# SCH_New_Project_2023-10-16.net
KiCad netlist of a schematic drawn in EasyEDA
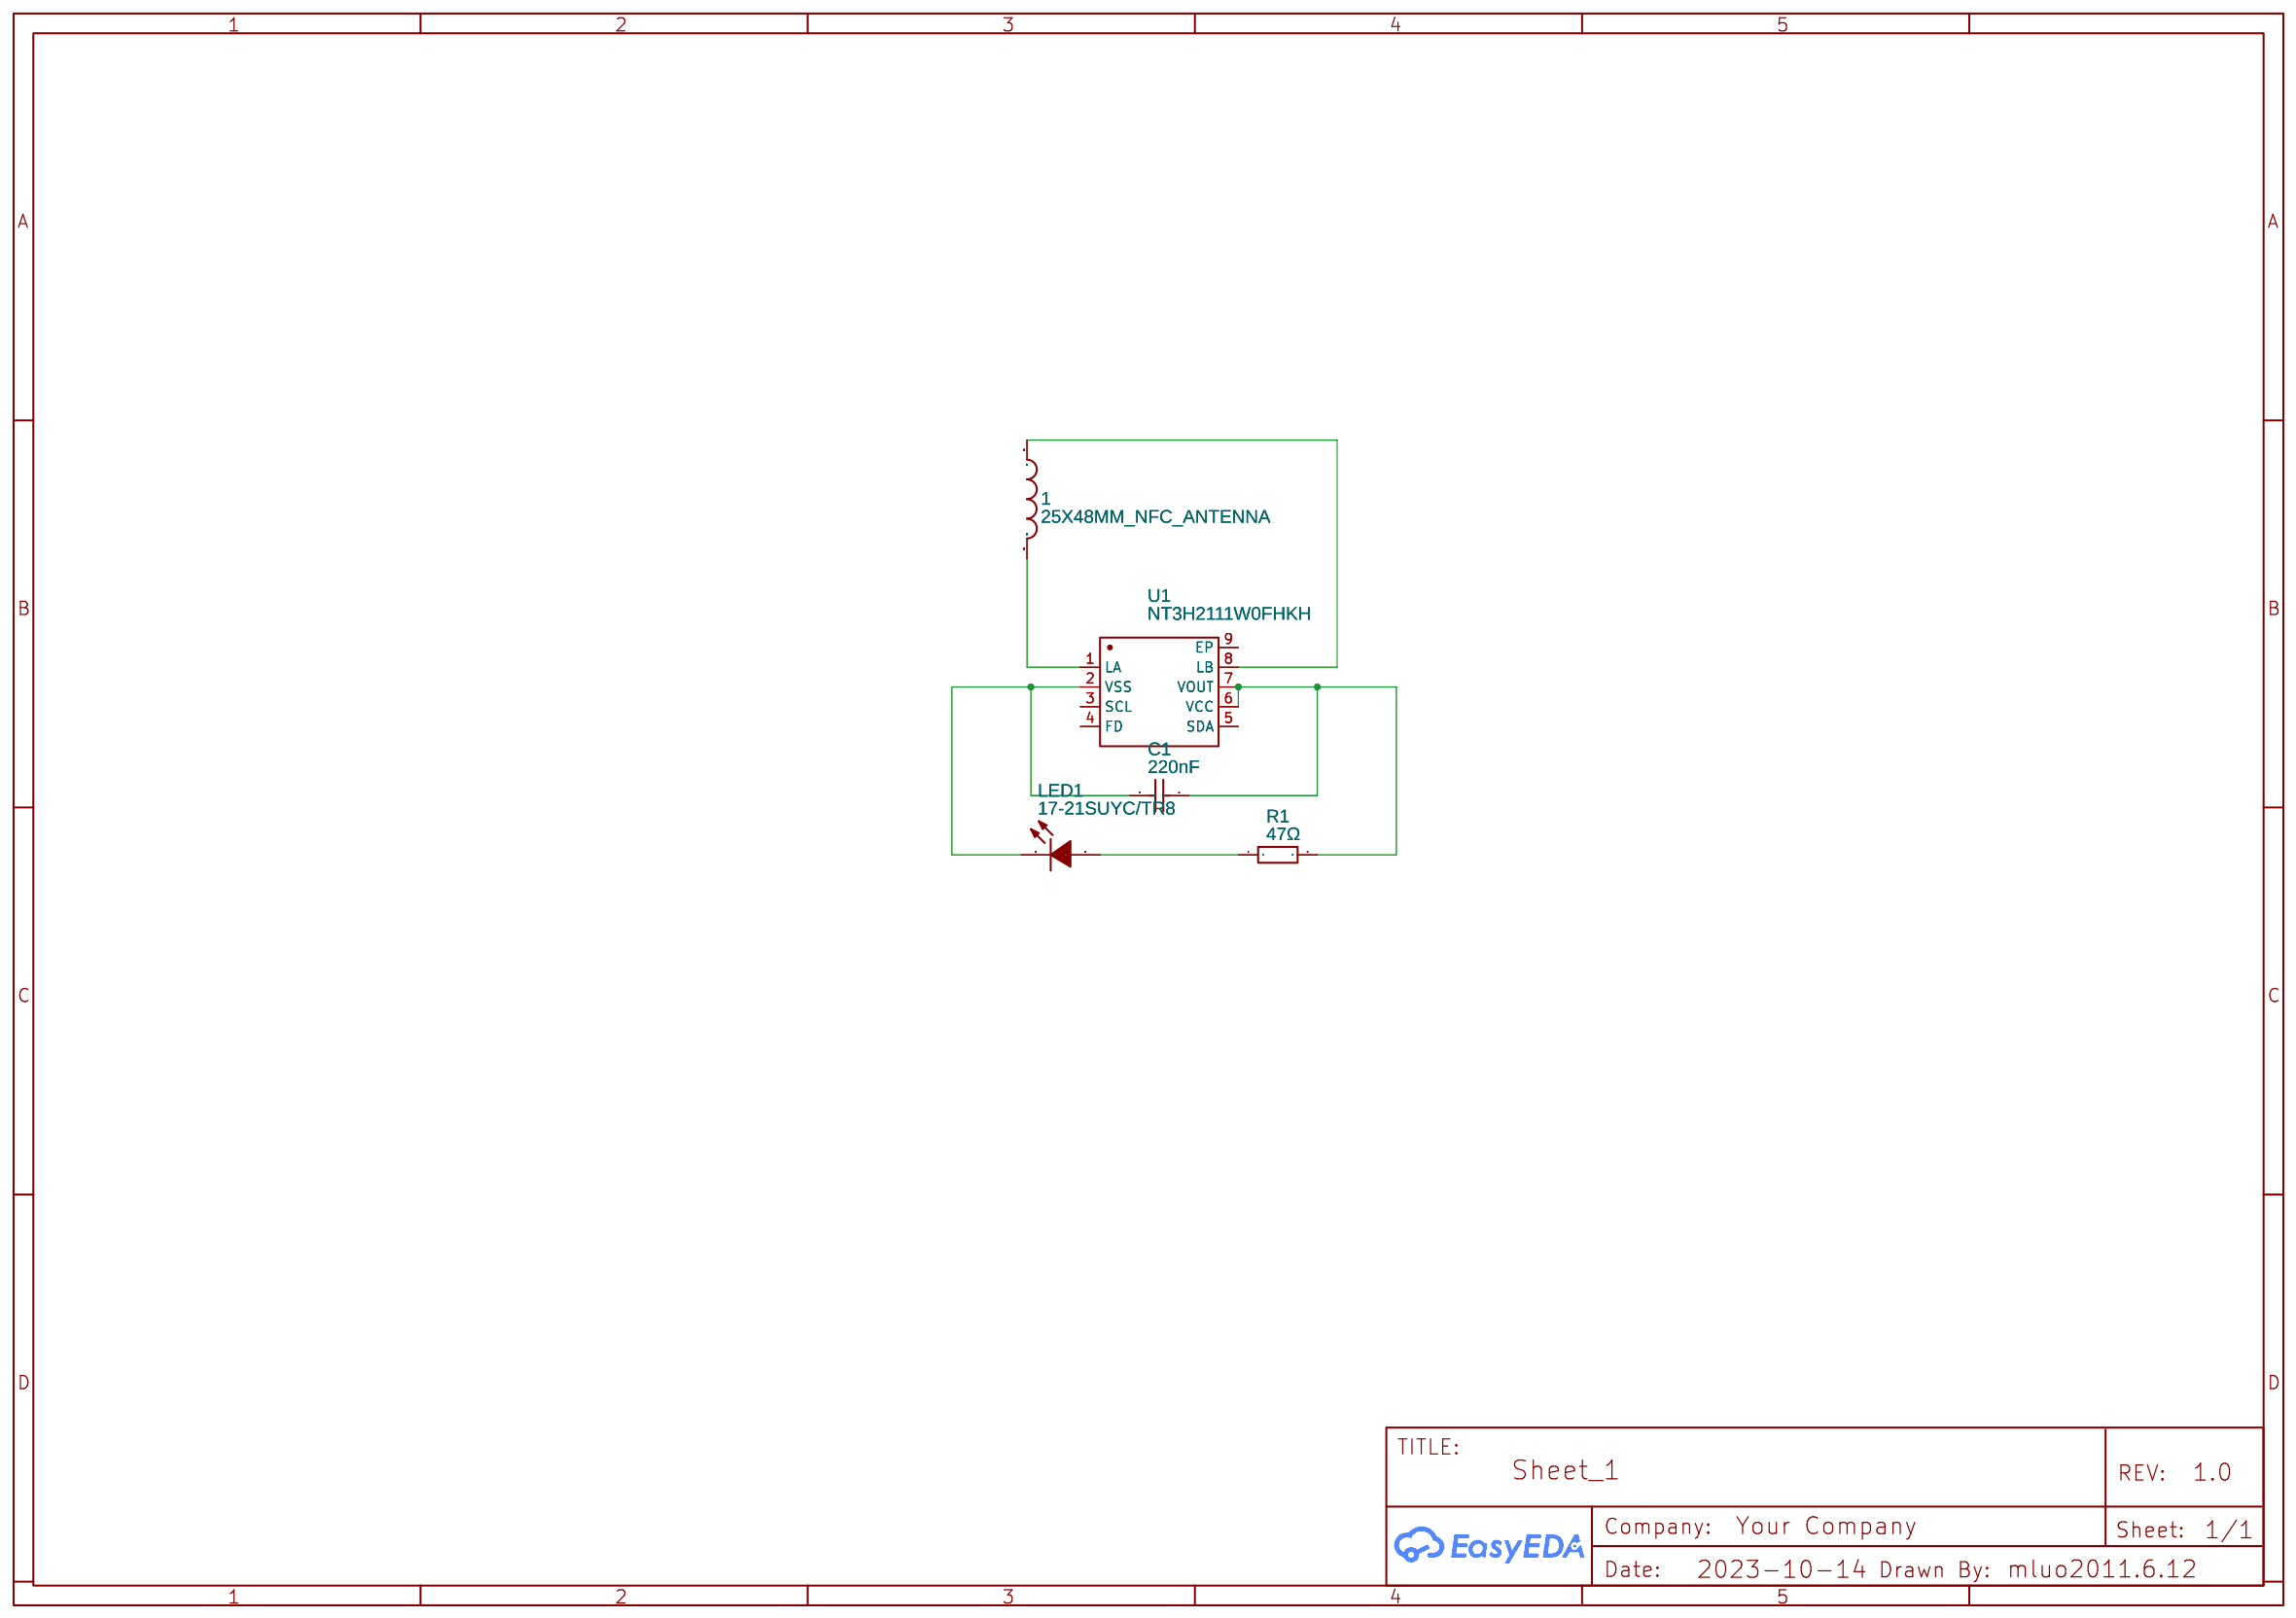
[diagram p0: schematic sheet]

(export (version "E")
  (design (tool "Eeschema 10.0.6"))
  (components
    (comp (ref "1") (value "25X48MM_NFC_ANTENNA") (libsource (lib "") (part "25X48MM_NFC_ANTENNA")))
    (comp (ref "C1")
      (value "220nF")
      (fields
        (field (name "Manufacturer Part") "CL10B224KA8NNNC")
        (field (name "Manufacturer") "SAMSUNG(三星)")
      )
      (libsource (lib "") (part "CL10B224KA8NNNC"))
    )
    (comp (ref "LED1")
      (value "17-21SUYC/TR8")
      (fields (field (name "Manufacturer Part") "KT-0805黄灯") (field (name "Manufacturer") "KENTO"))
      (libsource (lib "") (part "17-21SUYC/TR8"))
    )
    (comp (ref "R1")
      (value "47Ω")
      (fields
        (field (name "Manufacturer Part") "0603WAF470JT5E")
        (field (name "Manufacturer") "UNI-ROYAL(厚声)")
      )
      (libsource (lib "") (part "0603WAF470JT5E"))
    )
    (comp (ref "U1")
      (value "NT3H2111W0FHKH")
      (fields (field (name "Manufacturer") "NXP(恩智浦)"))
      (libsource (lib "") (part "NT3H2111W0FHKH"))
    )
  )
  (nets
    (net (code "1") (name "Net-(LED1-+)") (class "Default")
      (node (ref "LED1") (pin "1") (pinfunction "+_1") (pintype "unspecified"))
      (node (ref "R1") (pin "1") (pinfunction "1_1") (pintype "input"))
    )
    (net (code "2") (name "Net-(LED1--)") (class "Default")
      (node (ref "C1") (pin "1") (pinfunction "1_1") (pintype "input"))
      (node (ref "LED1") (pin "2") (pinfunction "-_2") (pintype "unspecified"))
      (node (ref "U1") (pin "2") (pinfunction "VSS_2") (pintype "unspecified"))
    )
    (net (code "3") (name "Net-(U1-LA)") (class "Default")
      (node (ref "1") (pin "P$2") (pinfunction "P$2_P$2") (pintype "bidirectional"))
      (node (ref "U1") (pin "1") (pinfunction "LA_1") (pintype "unspecified"))
    )
    (net (code "4") (name "Net-(U1-LB)") (class "Default")
      (node (ref "1") (pin "P$1") (pinfunction "P$1_P$1") (pintype "bidirectional"))
      (node (ref "U1") (pin "8") (pinfunction "LB_8") (pintype "unspecified"))
    )
    (net (code "5") (name "Net-(U1-VCC)") (class "Default")
      (node (ref "C1") (pin "2") (pinfunction "2_2") (pintype "input"))
      (node (ref "R1") (pin "2") (pinfunction "2_2") (pintype "input"))
      (node (ref "U1") (pin "6") (pinfunction "VCC_6") (pintype "unspecified"))
      (node (ref "U1") (pin "7") (pinfunction "VOUT_7") (pintype "unspecified"))
    )
    (net (code "6") (name "unconnected-(U1-EP-Pad9)") (class "Default")
      (node (ref "U1") (pin "9") (pinfunction "EP_9") (pintype "unspecified"))
    )
    (net (code "7") (name "unconnected-(U1-FD-Pad4)") (class "Default")
      (node (ref "U1") (pin "4") (pinfunction "FD_4") (pintype "unspecified"))
    )
    (net (code "8") (name "unconnected-(U1-SCL-Pad3)") (class "Default")
      (node (ref "U1") (pin "3") (pinfunction "SCL_3") (pintype "unspecified"))
    )
    (net (code "9") (name "unconnected-(U1-SDA-Pad5)") (class "Default")
      (node (ref "U1") (pin "5") (pinfunction "SDA_5") (pintype "unspecified"))
    )
  )
)
